# Dentist_camera_extender_schematic_sch_4.net
KiCad netlist of a schematic drawn in Altium Designer
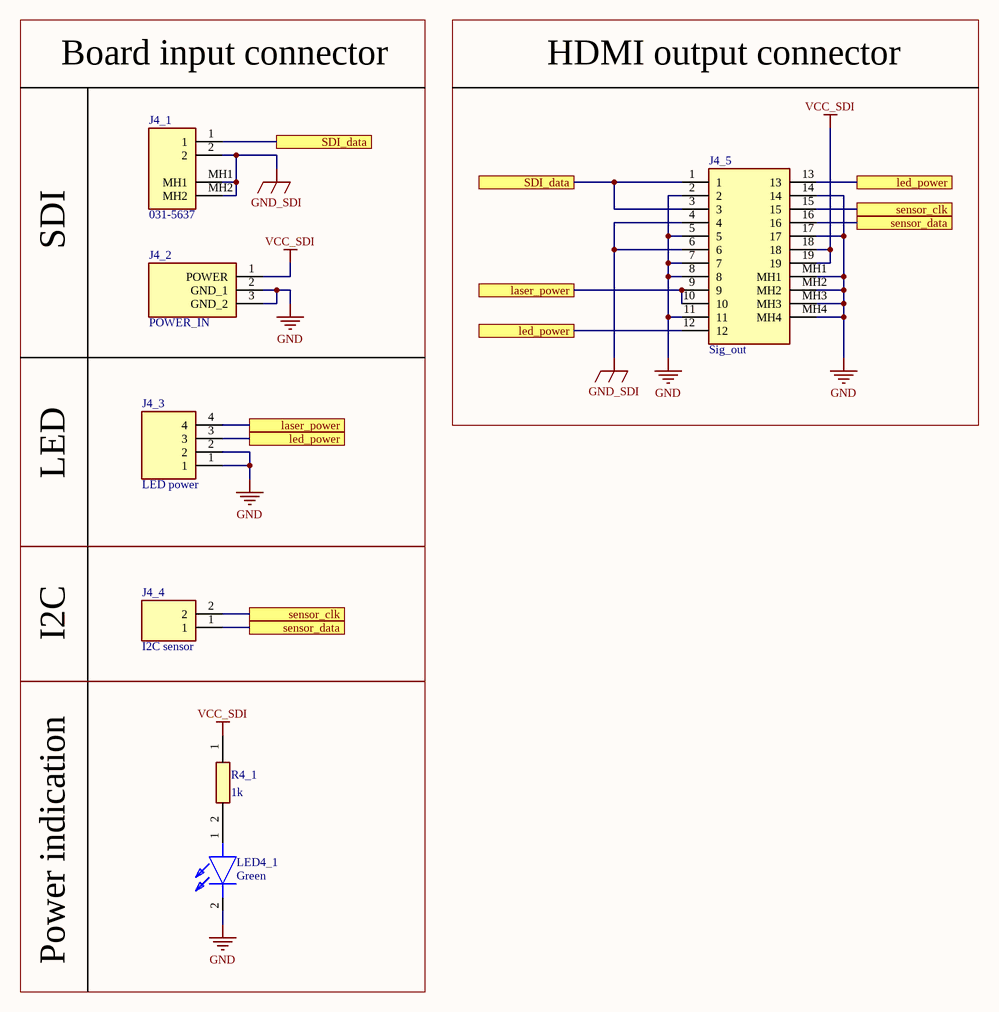
[diagram p0: Dentist_camera_extender_schematic_sch_4.SchDoc]

(export (version "E")
  (design (tool "Eeschema 10.0.6"))
  (components
    (comp (ref "J4_1")
      (value "031-5637")
      (footprint "SamacSys:0315637")
      (description "Connector")
      (fields (field (name "MOUSER PART NUMBER") "523-31-5637"))
      (libsource (lib "SamacSys") (part "031-5637"))
    )
    (comp (ref "J4_2")
      (value "POWER_IN")
      (footprint "SamacSys:694106301002_1")
      (description "694106301002")
      (fields (field (name "MOUSER PART NUMBER") "710-694106301002"))
      (libsource (lib "SamacSys") (part "694106301002"))
    )
    (comp (ref "J4_3")
      (value "LED power")
      (footprint "SamacSys:B04BJWPFSKRLFSN")
      (description "Connector")
      (fields (field (name "MANUFACTURER_PART_NUMBER") "B04B-JWPF-SK-R(LF)(SN)"))
      (libsource (lib "SamacSys") (part "B04B-JWPF-SK-R_LF__SN_"))
    )
    (comp (ref "J4_4")
      (value "I2C sensor")
      (footprint "SamacSys:B02BJWPFSKRLFSN")
      (description "Connector")
      (fields (field (name "MANUFACTURER_PART_NUMBER") "B02B-JWPF-SK-R(LF)(SN)"))
      (libsource (lib "SamacSys") (part "B02B-JWPF-SK-R_LF__SN_"))
    )
    (comp (ref "J4_5")
      (value "Sig_out")
      (footprint "SamacSys:10029449001RLF")
      (description "10029449-001RLF")
      (fields (field (name "MOUSER PART NUMBER") "649-10029449-001RLF"))
      (libsource (lib "SamacSys") (part "10029449-001RLF"))
    )
    (comp (ref "LED4_1")
      (value "Green")
      (footprint "SamacSys:1721SYGCS530E2TR8")
      (description "LED")
      (fields
        (field (name "MANUFACTURER_PART_NUMBER") "17-21SYGC/S530-E2/TR8")
        (field (name "MOUSER PART NUMBER") "638-1721SYGCS530E2")
      )
      (libsource (lib "SamacSys") (part "17-21SYGC_S530-E2_TR8"))
    )
    (comp (ref "R4_1")
      (value "1k")
      (footprint "SamacSys:ERA6AEB1020V")
      (description "ERA6ARB103V")
      (libsource (lib "SamacSys") (part "ERA6ARB103V"))
    )
  )
  (nets
    (net (code "1") (name "/SDI_data") (class "Default")
      (node (ref "J4_1") (pin "1") (pinfunction "1_1") (pintype "passive"))
      (node (ref "J4_5") (pin "1") (pinfunction "1_1") (pintype "passive"))
      (node (ref "J4_5") (pin "3") (pinfunction "3_3") (pintype "passive"))
    )
    (net (code "2") (name "/laser_power") (class "Default")
      (node (ref "J4_3") (pin "4") (pinfunction "4_4") (pintype "passive"))
      (node (ref "J4_5") (pin "10") (pinfunction "10_10") (pintype "passive"))
      (node (ref "J4_5") (pin "9") (pinfunction "9_9") (pintype "passive"))
    )
    (net (code "3") (name "/led_power") (class "Default")
      (node (ref "J4_3") (pin "3") (pinfunction "3_3") (pintype "passive"))
      (node (ref "J4_5") (pin "12") (pinfunction "12_12") (pintype "passive"))
      (node (ref "J4_5") (pin "13") (pinfunction "13_13") (pintype "passive"))
    )
    (net (code "4") (name "/sensor_clk") (class "Default")
      (node (ref "J4_4") (pin "2") (pinfunction "2_2") (pintype "passive"))
      (node (ref "J4_5") (pin "15") (pinfunction "15_15") (pintype "passive"))
    )
    (net (code "5") (name "/sensor_data") (class "Default")
      (node (ref "J4_4") (pin "1") (pinfunction "1_1") (pintype "passive"))
      (node (ref "J4_5") (pin "16") (pinfunction "16_16") (pintype "passive"))
    )
    (net (code "6") (name "GND") (class "Default")
      (node (ref "J4_2") (pin "2") (pinfunction "GND_1_2") (pintype "passive"))
      (node (ref "J4_2") (pin "3") (pinfunction "GND_2_3") (pintype "passive"))
      (node (ref "J4_3") (pin "1") (pinfunction "1_1") (pintype "passive"))
      (node (ref "J4_3") (pin "2") (pinfunction "2_2") (pintype "passive"))
      (node (ref "J4_5") (pin "11") (pinfunction "11_11") (pintype "passive"))
      (node (ref "J4_5") (pin "14") (pinfunction "14_14") (pintype "passive"))
      (node (ref "J4_5") (pin "17") (pinfunction "17_17") (pintype "passive"))
      (node (ref "J4_5") (pin "2") (pinfunction "2_2") (pintype "passive"))
      (node (ref "J4_5") (pin "5") (pinfunction "5_5") (pintype "passive"))
      (node (ref "J4_5") (pin "7") (pinfunction "7_7") (pintype "passive"))
      (node (ref "J4_5") (pin "8") (pinfunction "8_8") (pintype "passive"))
      (node (ref "J4_5") (pin "MH1") (pinfunction "MH1_MH1") (pintype "passive"))
      (node (ref "J4_5") (pin "MH2") (pinfunction "MH2_MH2") (pintype "passive"))
      (node (ref "J4_5") (pin "MH3") (pinfunction "MH3_MH3") (pintype "passive"))
      (node (ref "J4_5") (pin "MH4") (pinfunction "MH4_MH4") (pintype "passive"))
      (node (ref "LED4_1") (pin "2") (pinfunction "K_2") (pintype "passive"))
    )
    (net (code "7") (name "GND_SDI") (class "Default")
      (node (ref "J4_1") (pin "2") (pinfunction "2_2") (pintype "passive"))
      (node (ref "J4_1") (pin "MH1") (pinfunction "MH1_MH1") (pintype "passive"))
      (node (ref "J4_1") (pin "MH2") (pinfunction "MH2_MH2") (pintype "passive"))
      (node (ref "J4_5") (pin "4") (pinfunction "4_4") (pintype "passive"))
      (node (ref "J4_5") (pin "6") (pinfunction "6_6") (pintype "passive"))
    )
    (net (code "8") (name "Net-(LED4_1-A)") (class "Default")
      (node (ref "LED4_1") (pin "1") (pinfunction "A_1") (pintype "passive"))
      (node (ref "R4_1") (pin "2") (pinfunction "2_2") (pintype "passive"))
    )
    (net (code "9") (name "VCC_SDI") (class "Default")
      (node (ref "J4_2") (pin "1") (pinfunction "POWER_1") (pintype "passive"))
      (node (ref "J4_5") (pin "18") (pinfunction "18_18") (pintype "passive"))
      (node (ref "J4_5") (pin "19") (pinfunction "19_19") (pintype "passive"))
      (node (ref "R4_1") (pin "1") (pinfunction "1_1") (pintype "passive"))
    )
  )
)
